# Sheet2.net
KiCad netlist of a schematic drawn in Altium Designer
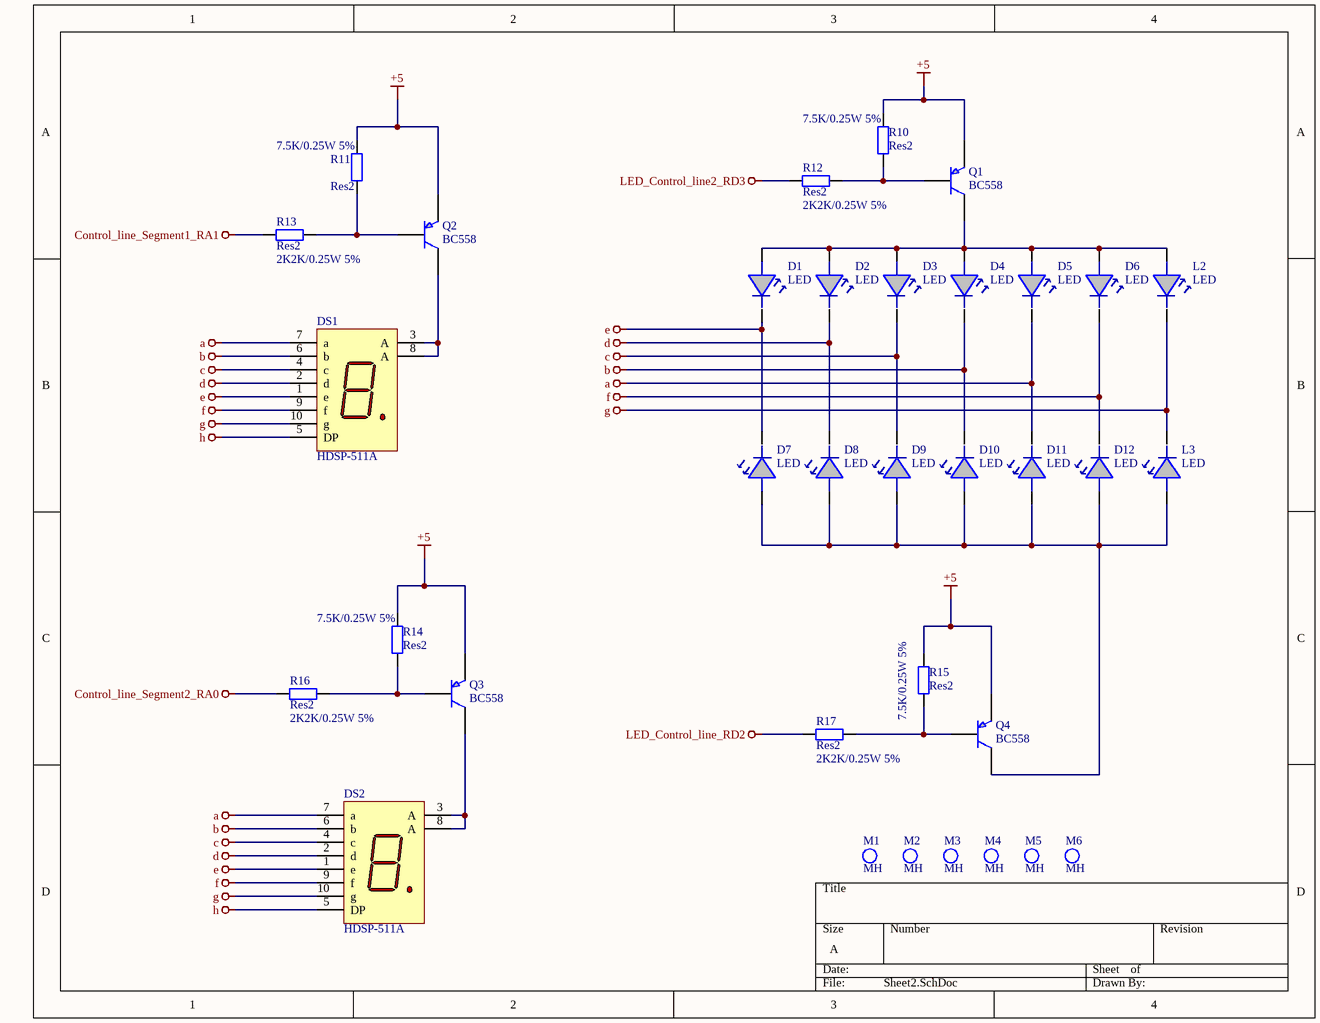
[diagram p0: Sheet2.SchDoc]

(export (version "E")
  (design (tool "Eeschema 10.0.6"))
  (components
    (comp (ref "D1")
      (value "LED")
      (footprint "LED5MM")
      (description "LED_5MM")
      (libsource (lib "Dinesh_New_Integrated_Library") (part "LED_5MM"))
    )
    (comp (ref "D2")
      (value "LED")
      (footprint "LED5MM")
      (description "LED_5MM")
      (libsource (lib "Dinesh_New_Integrated_Library") (part "LED_5MM"))
    )
    (comp (ref "D3")
      (value "LED")
      (footprint "LED5MM")
      (description "LED_5MM")
      (libsource (lib "Dinesh_New_Integrated_Library") (part "LED_5MM"))
    )
    (comp (ref "D4")
      (value "LED")
      (footprint "LED5MM")
      (description "LED_5MM")
      (libsource (lib "Dinesh_New_Integrated_Library") (part "LED_5MM"))
    )
    (comp (ref "D5")
      (value "LED")
      (footprint "LED5MM")
      (description "LED_5MM")
      (libsource (lib "Dinesh_New_Integrated_Library") (part "LED_5MM"))
    )
    (comp (ref "D6")
      (value "LED")
      (footprint "LED5MM")
      (description "LED_5MM")
      (libsource (lib "Dinesh_New_Integrated_Library") (part "LED_5MM"))
    )
    (comp (ref "D7")
      (value "LED")
      (footprint "LED5MM")
      (description "LED_5MM")
      (libsource (lib "Dinesh_New_Integrated_Library") (part "LED_5MM"))
    )
    (comp (ref "D8")
      (value "LED")
      (footprint "LED5MM")
      (description "LED_5MM")
      (libsource (lib "Dinesh_New_Integrated_Library") (part "LED_5MM"))
    )
    (comp (ref "D9")
      (value "LED")
      (footprint "LED5MM")
      (description "LED_5MM")
      (libsource (lib "Dinesh_New_Integrated_Library") (part "LED_5MM"))
    )
    (comp (ref "D10")
      (value "LED")
      (footprint "LED5MM")
      (description "LED_5MM")
      (libsource (lib "Dinesh_New_Integrated_Library") (part "LED_5MM"))
    )
    (comp (ref "D11")
      (value "LED")
      (footprint "LED5MM")
      (description "LED_5MM")
      (libsource (lib "Dinesh_New_Integrated_Library") (part "LED_5MM"))
    )
    (comp (ref "D12")
      (value "LED")
      (footprint "LED5MM")
      (description "LED_5MM")
      (libsource (lib "Dinesh_New_Integrated_Library") (part "LED_5MM"))
    )
    (comp (ref "DS1")
      (value "HDSP-511A")
      (footprint "HDSP-51")
      (description "14.22 mm General Purpose AlGaAs Red 7-Segment Display: CA, RH DP")
      (fields (field (name "PUBLISHER") "Altium Limited"))
      (libsource (lib "Agilent LED Display 7-Segment, 1-Digit") (part "HDSP-511A"))
    )
    (comp (ref "DS2")
      (value "HDSP-511A")
      (footprint "HDSP-51")
      (description "14.22 mm General Purpose AlGaAs Red 7-Segment Display: CA, RH DP")
      (fields (field (name "PUBLISHER") "Altium Limited"))
      (libsource (lib "Agilent LED Display 7-Segment, 1-Digit") (part "HDSP-511A"))
    )
    (comp (ref "L2")
      (value "LED")
      (footprint "LED5MM")
      (description "LED_5MM")
      (libsource (lib "Dinesh_New_Integrated_Library") (part "LED_5MM"))
    )
    (comp (ref "L3")
      (value "LED")
      (footprint "LED5MM")
      (description "LED_5MM")
      (libsource (lib "Dinesh_New_Integrated_Library") (part "LED_5MM"))
    )
    (comp (ref "M1")
      (value "MH")
      (footprint "Mounting hole")
      (libsource (lib "Dinesh_New_Integrated_Library") (part "MH"))
    )
    (comp (ref "M2")
      (value "MH")
      (footprint "Mounting hole")
      (libsource (lib "Dinesh_New_Integrated_Library") (part "MH"))
    )
    (comp (ref "M3")
      (value "MH")
      (footprint "Mounting hole")
      (libsource (lib "Dinesh_New_Integrated_Library") (part "MH"))
    )
    (comp (ref "M4")
      (value "MH")
      (footprint "Mounting hole")
      (libsource (lib "Dinesh_New_Integrated_Library") (part "MH"))
    )
    (comp (ref "M5")
      (value "MH")
      (footprint "Mounting hole")
      (libsource (lib "Dinesh_New_Integrated_Library") (part "MH"))
    )
    (comp (ref "M6")
      (value "MH")
      (footprint "Mounting hole")
      (libsource (lib "Dinesh_New_Integrated_Library") (part "MH"))
    )
    (comp (ref "Q1")
      (value "BC558")
      (footprint "TRANSISTOR_BC548")
      (description "PNP")
      (libsource (lib "Dinesh_New_Integrated_Library") (part "BC558"))
    )
    (comp (ref "Q2")
      (value "BC558")
      (footprint "TRANSISTOR_BC548")
      (description "PNP")
      (libsource (lib "Dinesh_New_Integrated_Library") (part "BC558"))
    )
    (comp (ref "Q3")
      (value "BC558")
      (footprint "TRANSISTOR_BC548")
      (description "PNP")
      (libsource (lib "Dinesh_New_Integrated_Library") (part "BC558"))
    )
    (comp (ref "Q4")
      (value "BC558")
      (footprint "TRANSISTOR_BC548")
      (description "PNP")
      (libsource (lib "Dinesh_New_Integrated_Library") (part "BC558"))
    )
    (comp (ref "R10")
      (value "Res2")
      (footprint "AXIAL-0.4")
      (description "Resistor")
      (fields (field (name "ALTIUM_VALUE") "7.5K/0.25W 5%") (field (name "PUBLISHER") "Altium Limited"))
      (libsource (lib "Miscellaneous Devices") (part "Res2"))
    )
    (comp (ref "R11")
      (value "Res2")
      (footprint "AXIAL-0.4")
      (description "Resistor")
      (fields (field (name "ALTIUM_VALUE") "7.5K/0.25W 5%") (field (name "PUBLISHER") "Altium Limited"))
      (libsource (lib "Miscellaneous Devices") (part "Res2"))
    )
    (comp (ref "R12")
      (value "Res2")
      (footprint "AXIAL-0.4")
      (description "Resistor")
      (fields (field (name "ALTIUM_VALUE") "2K2K/0.25W 5%") (field (name "PUBLISHER") "Altium Limited"))
      (libsource (lib "") (part "Res2_1"))
    )
    (comp (ref "R13")
      (value "Res2")
      (footprint "AXIAL-0.4")
      (description "Resistor")
      (fields (field (name "ALTIUM_VALUE") "2K2K/0.25W 5%") (field (name "PUBLISHER") "Altium Limited"))
      (libsource (lib "") (part "Res2_1"))
    )
    (comp (ref "R14")
      (value "Res2")
      (footprint "AXIAL-0.4")
      (description "Resistor")
      (fields (field (name "ALTIUM_VALUE") "7.5K/0.25W 5%") (field (name "PUBLISHER") "Altium Limited"))
      (libsource (lib "Miscellaneous Devices") (part "Res2"))
    )
    (comp (ref "R15")
      (value "Res2")
      (footprint "AXIAL-0.4")
      (description "Resistor")
      (fields (field (name "ALTIUM_VALUE") "7.5K/0.25W 5%") (field (name "PUBLISHER") "Altium Limited"))
      (libsource (lib "Miscellaneous Devices") (part "Res2"))
    )
    (comp (ref "R16")
      (value "Res2")
      (footprint "AXIAL-0.4")
      (description "Resistor")
      (fields (field (name "ALTIUM_VALUE") "2K2K/0.25W 5%") (field (name "PUBLISHER") "Altium Limited"))
      (libsource (lib "") (part "Res2_1"))
    )
    (comp (ref "R17")
      (value "Res2")
      (footprint "AXIAL-0.4")
      (description "Resistor")
      (fields (field (name "ALTIUM_VALUE") "2K2K/0.25W 5%") (field (name "PUBLISHER") "Altium Limited"))
      (libsource (lib "") (part "Res2_1"))
    )
  )
  (nets
    (net (code "1") (name "+5") (class "Default")
      (node (ref "Q1") (pin "3") (pinfunction "E_3") (pintype "passive"))
      (node (ref "Q2") (pin "3") (pinfunction "E_3") (pintype "passive"))
      (node (ref "Q3") (pin "3") (pinfunction "E_3") (pintype "passive"))
      (node (ref "Q4") (pin "3") (pinfunction "E_3") (pintype "passive"))
      (node (ref "R10") (pin "2") (pinfunction "2_2") (pintype "passive"))
      (node (ref "R11") (pin "2") (pinfunction "2_2") (pintype "passive"))
      (node (ref "R14") (pin "2") (pinfunction "2_2") (pintype "passive"))
      (node (ref "R15") (pin "2") (pinfunction "2_2") (pintype "passive"))
    )
    (net (code "2") (name "Control_line_Segment1_RA1") (class "Default")
      (node (ref "R13") (pin "2") (pinfunction "2_2") (pintype "passive"))
    )
    (net (code "3") (name "Control_line_Segment2_RA0") (class "Default")
      (node (ref "R16") (pin "2") (pinfunction "2_2") (pintype "passive"))
    )
    (net (code "4") (name "LED_Control_line2_RD3") (class "Default")
      (node (ref "R12") (pin "2") (pinfunction "2_2") (pintype "passive"))
    )
    (net (code "5") (name "LED_Control_line_RD2") (class "Default")
      (node (ref "R17") (pin "2") (pinfunction "2_2") (pintype "passive"))
    )
    (net (code "6") (name "Net-(D1-A)") (class "Default")
      (node (ref "D1") (pin "1") (pinfunction "A_1") (pintype "passive"))
      (node (ref "D2") (pin "1") (pinfunction "A_1") (pintype "passive"))
      (node (ref "D3") (pin "1") (pinfunction "A_1") (pintype "passive"))
      (node (ref "D4") (pin "1") (pinfunction "A_1") (pintype "passive"))
      (node (ref "D5") (pin "1") (pinfunction "A_1") (pintype "passive"))
      (node (ref "D6") (pin "1") (pinfunction "A_1") (pintype "passive"))
      (node (ref "L2") (pin "1") (pinfunction "A_1") (pintype "passive"))
      (node (ref "Q1") (pin "1") (pinfunction "C_1") (pintype "passive"))
    )
    (net (code "7") (name "Net-(D10-A)") (class "Default")
      (node (ref "D10") (pin "1") (pinfunction "A_1") (pintype "passive"))
      (node (ref "D11") (pin "1") (pinfunction "A_1") (pintype "passive"))
      (node (ref "D12") (pin "1") (pinfunction "A_1") (pintype "passive"))
      (node (ref "D7") (pin "1") (pinfunction "A_1") (pintype "passive"))
      (node (ref "D8") (pin "1") (pinfunction "A_1") (pintype "passive"))
      (node (ref "D9") (pin "1") (pinfunction "A_1") (pintype "passive"))
      (node (ref "L3") (pin "1") (pinfunction "A_1") (pintype "passive"))
      (node (ref "Q4") (pin "1") (pinfunction "C_1") (pintype "passive"))
    )
    (net (code "8") (name "Net-(Q1-B)") (class "Default")
      (node (ref "Q1") (pin "2") (pinfunction "B_2") (pintype "passive"))
      (node (ref "R10") (pin "1") (pinfunction "1_1") (pintype "passive"))
      (node (ref "R12") (pin "1") (pinfunction "1_1") (pintype "passive"))
    )
    (net (code "9") (name "Net-(Q2-B)") (class "Default")
      (node (ref "Q2") (pin "2") (pinfunction "B_2") (pintype "passive"))
      (node (ref "R11") (pin "1") (pinfunction "1_1") (pintype "passive"))
      (node (ref "R13") (pin "1") (pinfunction "1_1") (pintype "passive"))
    )
    (net (code "10") (name "Net-(Q2-C)") (class "Default")
      (node (ref "DS1") (pin "3") (pinfunction "A_3") (pintype "passive"))
      (node (ref "DS1") (pin "8") (pinfunction "A_8") (pintype "passive"))
      (node (ref "Q2") (pin "1") (pinfunction "C_1") (pintype "passive"))
    )
    (net (code "11") (name "Net-(Q3-B)") (class "Default")
      (node (ref "Q3") (pin "2") (pinfunction "B_2") (pintype "passive"))
      (node (ref "R14") (pin "1") (pinfunction "1_1") (pintype "passive"))
      (node (ref "R16") (pin "1") (pinfunction "1_1") (pintype "passive"))
    )
    (net (code "12") (name "Net-(Q3-C)") (class "Default")
      (node (ref "DS2") (pin "3") (pinfunction "A_3") (pintype "passive"))
      (node (ref "DS2") (pin "8") (pinfunction "A_8") (pintype "passive"))
      (node (ref "Q3") (pin "1") (pinfunction "C_1") (pintype "passive"))
    )
    (net (code "13") (name "Net-(Q4-B)") (class "Default")
      (node (ref "Q4") (pin "2") (pinfunction "B_2") (pintype "passive"))
      (node (ref "R15") (pin "1") (pinfunction "1_1") (pintype "passive"))
      (node (ref "R17") (pin "1") (pinfunction "1_1") (pintype "passive"))
    )
    (net (code "14") (name "a") (class "Default")
      (node (ref "D11") (pin "2") (pinfunction "B_2") (pintype "passive"))
      (node (ref "D5") (pin "2") (pinfunction "B_2") (pintype "passive"))
      (node (ref "DS1") (pin "7") (pinfunction "a_7") (pintype "passive"))
      (node (ref "DS2") (pin "7") (pinfunction "a_7") (pintype "passive"))
    )
    (net (code "15") (name "b") (class "Default")
      (node (ref "D10") (pin "2") (pinfunction "B_2") (pintype "passive"))
      (node (ref "D4") (pin "2") (pinfunction "B_2") (pintype "passive"))
      (node (ref "DS1") (pin "6") (pinfunction "b_6") (pintype "passive"))
      (node (ref "DS2") (pin "6") (pinfunction "b_6") (pintype "passive"))
    )
    (net (code "16") (name "c") (class "Default")
      (node (ref "D3") (pin "2") (pinfunction "B_2") (pintype "passive"))
      (node (ref "D9") (pin "2") (pinfunction "B_2") (pintype "passive"))
      (node (ref "DS1") (pin "4") (pinfunction "c_4") (pintype "passive"))
      (node (ref "DS2") (pin "4") (pinfunction "c_4") (pintype "passive"))
    )
    (net (code "17") (name "d") (class "Default")
      (node (ref "D2") (pin "2") (pinfunction "B_2") (pintype "passive"))
      (node (ref "D8") (pin "2") (pinfunction "B_2") (pintype "passive"))
      (node (ref "DS1") (pin "2") (pinfunction "d_2") (pintype "passive"))
      (node (ref "DS2") (pin "2") (pinfunction "d_2") (pintype "passive"))
    )
    (net (code "18") (name "e") (class "Default")
      (node (ref "D1") (pin "2") (pinfunction "B_2") (pintype "passive"))
      (node (ref "D7") (pin "2") (pinfunction "B_2") (pintype "passive"))
      (node (ref "DS1") (pin "1") (pinfunction "e_1") (pintype "passive"))
      (node (ref "DS2") (pin "1") (pinfunction "e_1") (pintype "passive"))
    )
    (net (code "19") (name "f") (class "Default")
      (node (ref "D12") (pin "2") (pinfunction "B_2") (pintype "passive"))
      (node (ref "D6") (pin "2") (pinfunction "B_2") (pintype "passive"))
      (node (ref "DS1") (pin "9") (pinfunction "f_9") (pintype "passive"))
      (node (ref "DS2") (pin "9") (pinfunction "f_9") (pintype "passive"))
    )
    (net (code "20") (name "g") (class "Default")
      (node (ref "DS1") (pin "10") (pinfunction "g_10") (pintype "passive"))
      (node (ref "DS2") (pin "10") (pinfunction "g_10") (pintype "passive"))
      (node (ref "L2") (pin "2") (pinfunction "B_2") (pintype "passive"))
      (node (ref "L3") (pin "2") (pinfunction "B_2") (pintype "passive"))
    )
    (net (code "21") (name "h") (class "Default")
      (node (ref "DS1") (pin "5") (pinfunction "DP_5") (pintype "passive"))
      (node (ref "DS2") (pin "5") (pinfunction "DP_5") (pintype "passive"))
    )
  )
)
